# ReflowController.net
KiCad netlist of a schematic drawn in EAGLE
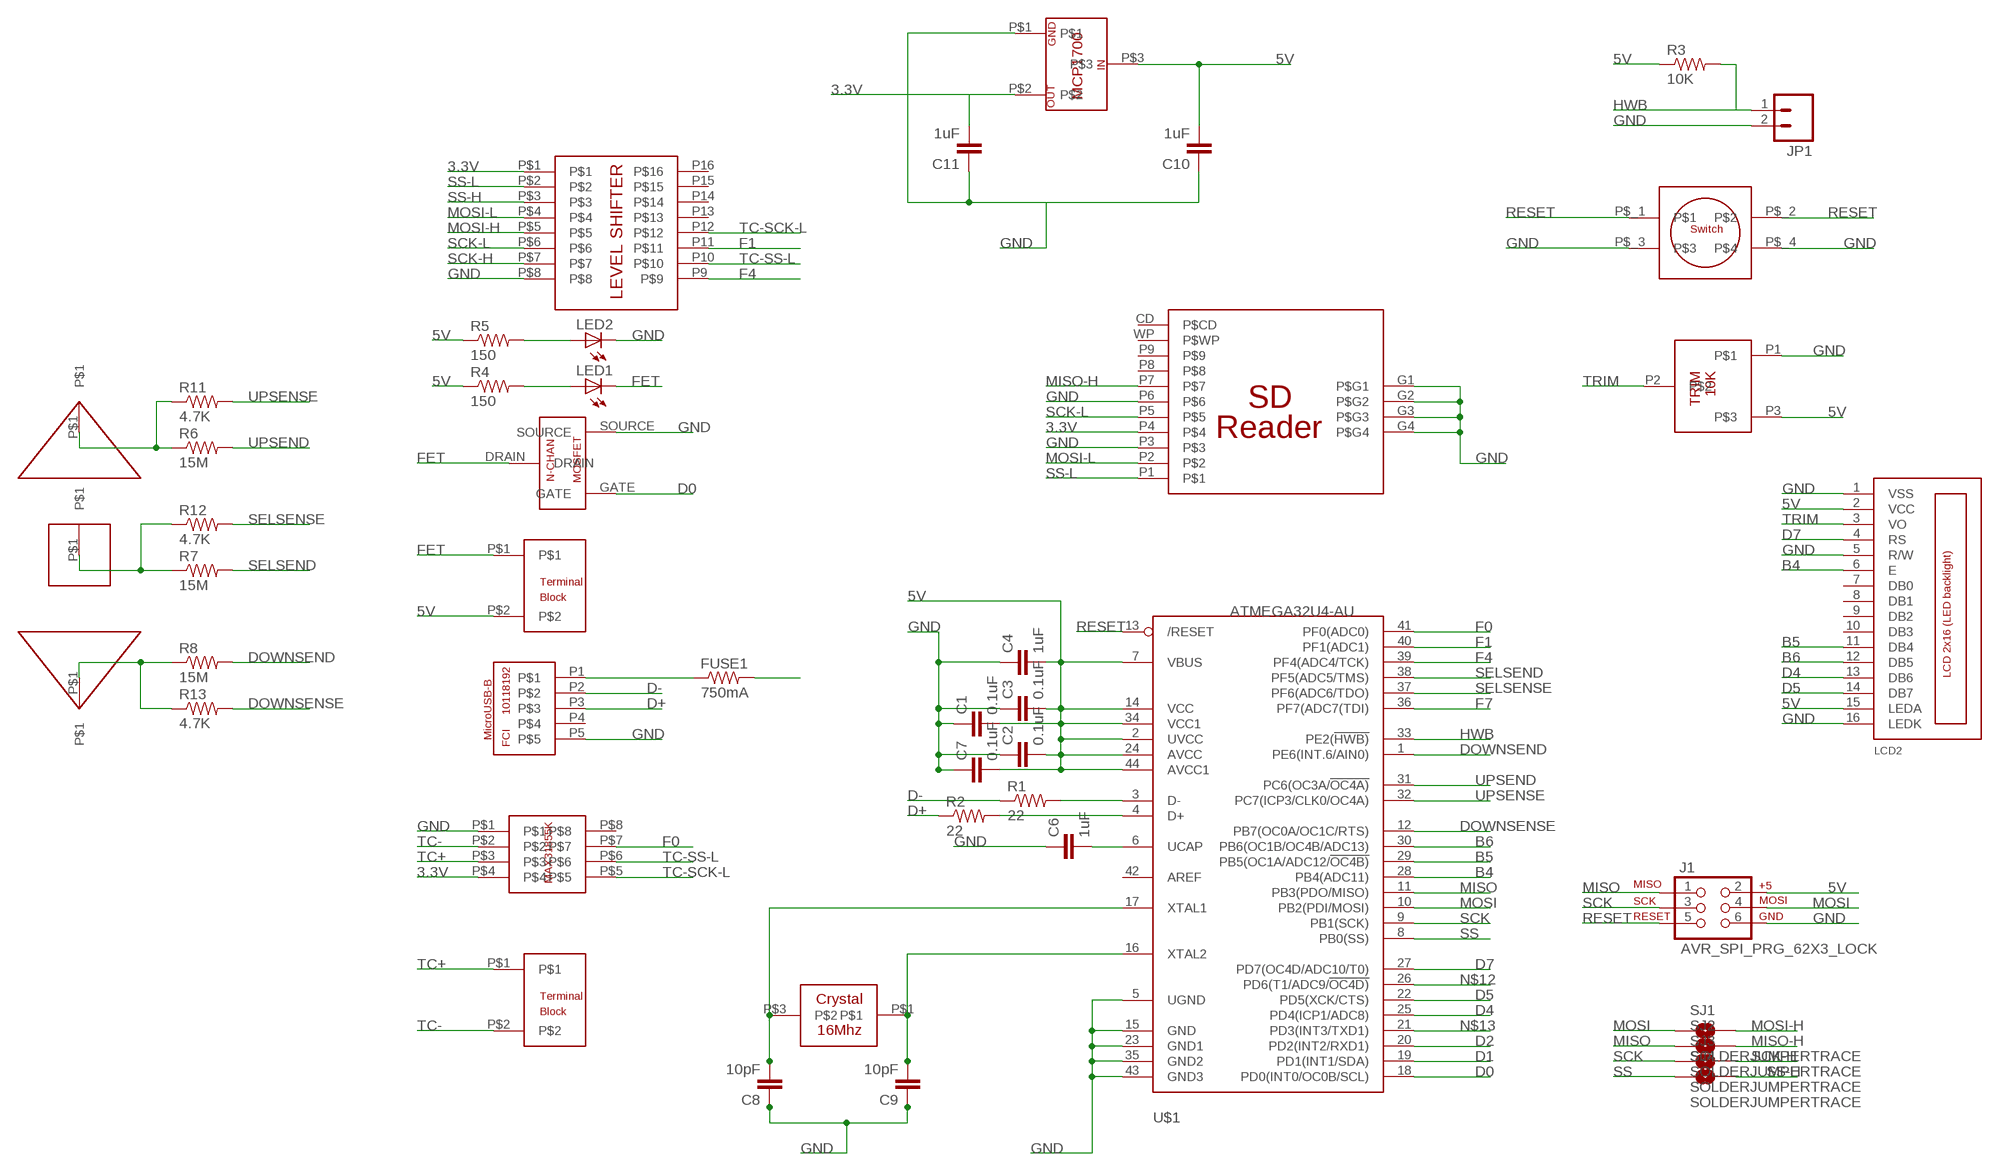
[diagram p0: schematic, sheet 1]

(export (version "E")
  (design (tool "Eeschema 10.0.6"))
  (components
    (comp (ref "C1")
      (value "0.1uF")
      (footprint "eagle-import:0603-CAP")
      (libsource (lib "eagle-import") (part "CAP0603-CAP"))
    )
    (comp (ref "C2")
      (value "0.1uF")
      (footprint "eagle-import:0603-CAP")
      (libsource (lib "eagle-import") (part "CAP0603-CAP"))
    )
    (comp (ref "C3")
      (value "0.1uF")
      (footprint "eagle-import:0603-CAP")
      (libsource (lib "eagle-import") (part "CAP0603-CAP"))
    )
    (comp (ref "C4")
      (value "1uF")
      (footprint "eagle-import:0603-CAP")
      (libsource (lib "eagle-import") (part "CAP0603-CAP"))
    )
    (comp (ref "C6")
      (value "1uF")
      (footprint "eagle-import:0603-CAP")
      (libsource (lib "eagle-import") (part "CAP0603-CAP"))
    )
    (comp (ref "C7")
      (value "0.1uF")
      (footprint "eagle-import:0603-CAP")
      (libsource (lib "eagle-import") (part "CAP0603-CAP"))
    )
    (comp (ref "C8")
      (value "10pF")
      (footprint "eagle-import:0603-CAP")
      (libsource (lib "eagle-import") (part "CAP0603-CAP"))
    )
    (comp (ref "C9")
      (value "10pF")
      (footprint "eagle-import:0603-CAP")
      (libsource (lib "eagle-import") (part "CAP0603-CAP"))
    )
    (comp (ref "C10")
      (value "1uF")
      (footprint "eagle-import:0603-CAP")
      (libsource (lib "eagle-import") (part "CAP0603-CAP"))
    )
    (comp (ref "C11")
      (value "1uF")
      (footprint "eagle-import:0603-CAP")
      (libsource (lib "eagle-import") (part "CAP0603-CAP"))
    )
    (comp (ref "FUSE1")
      (value "750mA")
      (footprint "eagle-import:0603-RES")
      (libsource (lib "eagle-import") (part "RESISTOR0603-RES"))
    )
    (comp (ref "J1")
      (value "AVR_SPI_PRG_62X3_LOCK")
      (footprint "eagle-import:2X3_LOCK")
      (libsource (lib "eagle-import") (part "AVR_SPI_PRG_62X3_LOCK"))
    )
    (comp (ref "JP1")
      (value "M02PTH")
      (footprint "eagle-import:1X02")
      (libsource (lib "eagle-import") (part "M02PTH"))
    )
    (comp (ref "LCD2")
      (value "LCD_2X16_SIL")
      (footprint "eagle-import:HY-1602F")
      (libsource (lib "eagle-import") (part "LCD_2X16_SIL"))
    )
    (comp (ref "LED1")
      (value "LED0603")
      (footprint "eagle-import:LED-0603")
      (libsource (lib "eagle-import") (part "LED0603"))
    )
    (comp (ref "LED2")
      (value "LED0603")
      (footprint "eagle-import:LED-0603")
      (libsource (lib "eagle-import") (part "LED0603"))
    )
    (comp (ref "R1")
      (value "22")
      (footprint "eagle-import:0603-RES")
      (libsource (lib "eagle-import") (part "RESISTOR0603-RES"))
    )
    (comp (ref "R2")
      (value "22")
      (footprint "eagle-import:0603-RES")
      (libsource (lib "eagle-import") (part "RESISTOR0603-RES"))
    )
    (comp (ref "R3")
      (value "10K")
      (footprint "eagle-import:0603-RES")
      (libsource (lib "eagle-import") (part "RESISTOR0603-RES"))
    )
    (comp (ref "R4")
      (value "150")
      (footprint "eagle-import:0603-RES")
      (libsource (lib "eagle-import") (part "RESISTOR0603-RES"))
    )
    (comp (ref "R5")
      (value "150")
      (footprint "eagle-import:0603-RES")
      (libsource (lib "eagle-import") (part "RESISTOR0603-RES"))
    )
    (comp (ref "R6")
      (value "15M")
      (footprint "eagle-import:0603-RES")
      (libsource (lib "eagle-import") (part "RESISTOR0603-RES"))
    )
    (comp (ref "R7")
      (value "15M")
      (footprint "eagle-import:0603-RES")
      (libsource (lib "eagle-import") (part "RESISTOR0603-RES"))
    )
    (comp (ref "R8")
      (value "15M")
      (footprint "eagle-import:0603-RES")
      (libsource (lib "eagle-import") (part "RESISTOR0603-RES"))
    )
    (comp (ref "R11")
      (value "4.7K")
      (footprint "eagle-import:0603-RES")
      (libsource (lib "eagle-import") (part "RESISTOR0603-RES"))
    )
    (comp (ref "R12")
      (value "4.7K")
      (footprint "eagle-import:0603-RES")
      (libsource (lib "eagle-import") (part "RESISTOR0603-RES"))
    )
    (comp (ref "R13")
      (value "4.7K")
      (footprint "eagle-import:0603-RES")
      (libsource (lib "eagle-import") (part "RESISTOR0603-RES"))
    )
    (comp (ref "SJ1")
      (value "SOLDERJUMPERTRACE")
      (footprint "eagle-import:SJ_2S-TRACE")
      (libsource (lib "eagle-import") (part "SOLDERJUMPERTRACE"))
    )
    (comp (ref "SJ2")
      (value "SOLDERJUMPERTRACE")
      (footprint "eagle-import:SJ_2S-TRACE")
      (libsource (lib "eagle-import") (part "SOLDERJUMPERTRACE"))
    )
    (comp (ref "SJ3")
      (value "SOLDERJUMPERTRACE")
      (footprint "eagle-import:SJ_2S-TRACE")
      (libsource (lib "eagle-import") (part "SOLDERJUMPERTRACE"))
    )
    (comp (ref "SJ4")
      (value "SOLDERJUMPERTRACE")
      (footprint "eagle-import:SJ_2S-TRACE")
      (libsource (lib "eagle-import") (part "SOLDERJUMPERTRACE"))
    )
    (comp (ref "U$1")
      (value "ATMEGA32U4-AU")
      (footprint "eagle-import:TQFP44")
      (libsource (lib "eagle-import") (part "ATMEGA32U4-AU"))
    )
    (comp (ref "U$2")
      (value "16MHZ-CRYSTAL_NX3225GA-16.000M-STD-CRG-1")
      (footprint "eagle-import:16MHZ-CRYSTAL_NX3225GA-16.000M-STD-CRG-1")
      (libsource (lib "eagle-import") (part "16MHZ-CRYSTAL_NX3225GA-16.000M-STD-CRG-1"))
    )
    (comp (ref "U$3")
      (value "USB-B_10118192-0001LF")
      (footprint "eagle-import:USB-B_10118192-0001LF")
      (libsource (lib "eagle-import") (part "USB-B_10118192-0001LF"))
    )
    (comp (ref "U$4")
      (value "SDREADER_2041021-4")
      (footprint "eagle-import:SDREADER_2041021-4")
      (libsource (lib "eagle-import") (part "SDREADER_2041021-4"))
    )
    (comp (ref "U$5")
      (value "2POS_TERM_ED2748-ND")
      (footprint "eagle-import:2POS_TERM_ED2748-ND")
      (libsource (lib "eagle-import") (part "2POS_TERM_ED2748-ND"))
    )
    (comp (ref "U$6")
      (value "N-MOSFET630_DMG1012T-7DICT-ND")
      (footprint "eagle-import:N-MOSFET630_DMG1012T-7DICT-ND")
      (libsource (lib "eagle-import") (part "N-MOSFET630_DMG1012T-7DICT-ND"))
    )
    (comp (ref "U$7")
      (value "2POS_TERM_ED2748-ND")
      (footprint "eagle-import:2POS_TERM_ED2748-ND")
      (libsource (lib "eagle-import") (part "2POS_TERM_ED2748-ND"))
    )
    (comp (ref "U$8")
      (value "NXP_LVL_SHIFT_74HC4050D,653")
      (footprint "eagle-import:NXP_LVL_SHIFT_74HC4050D,653")
      (libsource (lib "eagle-import") (part "NXP_LVL_SHIFT_74HC4050D,653"))
    )
    (comp (ref "U$9")
      (value "MAX_TC_MAX31855KASA+")
      (footprint "eagle-import:MAX_TC_MAX31855KASA+")
      (libsource (lib "eagle-import") (part "MAX_TC_MAX31855KASA+"))
    )
    (comp (ref "U$10")
      (value "10K_TRIM_3362F-1-103LF")
      (footprint "eagle-import:10K_TRIM_3362F-1-103LF")
      (libsource (lib "eagle-import") (part "10K_TRIM_3362F-1-103LF"))
    )
    (comp (ref "U$11")
      (value "MCP1700__LDO")
      (footprint "eagle-import:MCP1700__LDO")
      (libsource (lib "eagle-import") (part "MCP1700__LDO"))
    )
    (comp (ref "U$12")
      (value "MOM-SWITCH-EG4620CT-ND")
      (footprint "eagle-import:MOM-SWITCH-EG4620CT-ND")
      (libsource (lib "eagle-import") (part "MOM-SWITCH-EG4620CT-ND"))
    )
    (comp (ref "U$13")
      (value "CAPTOUCH_ARROW")
      (footprint "eagle-import:CAPTOUCH_ARROW")
      (libsource (lib "eagle-import") (part "CAPTOUCH_ARROW"))
    )
    (comp (ref "U$14")
      (value "CAPTOUCH_ARROW")
      (footprint "eagle-import:CAPTOUCH_ARROW")
      (libsource (lib "eagle-import") (part "CAPTOUCH_ARROW"))
    )
    (comp (ref "U$15")
      (value "CAPTOUCH_SQUARE")
      (footprint "eagle-import:CAPTOUCH_SQUARE")
      (libsource (lib "eagle-import") (part "CAPTOUCH_SQUARE"))
    )
  )
  (nets
    (net (code "1") (name "/3.3V") (class "Default")
      (node (ref "C11") (pin "2") (pinfunction "2_2") (pintype "passive"))
      (node (ref "U$11") (pin "P$2") (pinfunction "P$2_P$2") (pintype "bidirectional"))
      (node (ref "U$4") (pin "P4") (pinfunction "P$4_P4") (pintype "bidirectional"))
      (node (ref "U$8") (pin "P$1") (pinfunction "P$1_P$1") (pintype "bidirectional"))
      (node (ref "U$9") (pin "P$4") (pinfunction "P$4_P$4") (pintype "bidirectional"))
    )
    (net (code "2") (name "/5V") (class "Default")
      (node (ref "C1") (pin "2") (pinfunction "2_2") (pintype "passive"))
      (node (ref "C10") (pin "2") (pinfunction "2_2") (pintype "passive"))
      (node (ref "C2") (pin "2") (pinfunction "2_2") (pintype "passive"))
      (node (ref "C3") (pin "2") (pinfunction "2_2") (pintype "passive"))
      (node (ref "C4") (pin "2") (pinfunction "2_2") (pintype "passive"))
      (node (ref "C7") (pin "2") (pinfunction "2_2") (pintype "passive"))
      (node (ref "FUSE1") (pin "2") (pinfunction "2_2") (pintype "passive"))
      (node (ref "J1") (pin "2") (pinfunction "2_2") (pintype "passive"))
      (node (ref "LCD2") (pin "15") (pinfunction "LEDA_15") (pintype "passive"))
      (node (ref "LCD2") (pin "2") (pinfunction "VCC_2") (pintype "power_in"))
      (node (ref "R3") (pin "1") (pinfunction "1_1") (pintype "passive"))
      (node (ref "R4") (pin "1") (pinfunction "1_1") (pintype "passive"))
      (node (ref "R5") (pin "1") (pinfunction "1_1") (pintype "passive"))
      (node (ref "U$1") (pin "14") (pinfunction "VCC_14") (pintype "bidirectional"))
      (node (ref "U$1") (pin "2") (pinfunction "UVCC_2") (pintype "bidirectional"))
      (node (ref "U$1") (pin "24") (pinfunction "AVCC_24") (pintype "bidirectional"))
      (node (ref "U$1") (pin "34") (pinfunction "VCC1_34") (pintype "bidirectional"))
      (node (ref "U$1") (pin "44") (pinfunction "AVCC1_44") (pintype "bidirectional"))
      (node (ref "U$1") (pin "7") (pinfunction "VBUS_7") (pintype "bidirectional"))
      (node (ref "U$10") (pin "P3") (pinfunction "P$3_P3") (pintype "bidirectional"))
      (node (ref "U$11") (pin "P$3") (pinfunction "P$3_P$3") (pintype "bidirectional"))
      (node (ref "U$5") (pin "P$2") (pinfunction "P$2_P$2") (pintype "bidirectional"))
    )
    (net (code "3") (name "/B4") (class "Default")
      (node (ref "LCD2") (pin "6") (pinfunction "E_6") (pintype "input"))
      (node (ref "U$1") (pin "28") (pinfunction "PB4(ADC11)_28") (pintype "bidirectional"))
    )
    (net (code "4") (name "/B5") (class "Default")
      (node (ref "LCD2") (pin "11") (pinfunction "DB4_11") (pintype "bidirectional"))
      (node (ref "U$1") (pin "29") (pinfunction "PB5(OC1A/ADC12/~{OC4B})_29") (pintype "bidirectional"))
    )
    (net (code "5") (name "/B6") (class "Default")
      (node (ref "LCD2") (pin "12") (pinfunction "DB5_12") (pintype "bidirectional"))
      (node (ref "U$1") (pin "30") (pinfunction "PB6(OC1B/OC4B/ADC13)_30") (pintype "bidirectional"))
    )
    (net (code "6") (name "/D+") (class "Default")
      (node (ref "R2") (pin "1") (pinfunction "1_1") (pintype "passive"))
      (node (ref "U$3") (pin "P3") (pinfunction "P$3_P3") (pintype "bidirectional"))
    )
    (net (code "7") (name "/D-") (class "Default")
      (node (ref "R1") (pin "1") (pinfunction "1_1") (pintype "passive"))
      (node (ref "U$3") (pin "P2") (pinfunction "P$2_P2") (pintype "bidirectional"))
    )
    (net (code "8") (name "/D0") (class "Default")
      (node (ref "U$1") (pin "18") (pinfunction "PD0(INT0/OC0B/SCL)_18") (pintype "bidirectional"))
      (node (ref "U$6") (pin "GATE") (pinfunction "GATE_GATE") (pintype "bidirectional"))
    )
    (net (code "9") (name "/D1") (class "Default")
      (node (ref "U$1") (pin "19") (pinfunction "PD1(INT1/SDA)_19") (pintype "bidirectional"))
    )
    (net (code "10") (name "/D2") (class "Default")
      (node (ref "U$1") (pin "20") (pinfunction "PD2(INT2/RXD1)_20") (pintype "bidirectional"))
    )
    (net (code "11") (name "/D4") (class "Default")
      (node (ref "LCD2") (pin "13") (pinfunction "DB6_13") (pintype "bidirectional"))
      (node (ref "U$1") (pin "25") (pinfunction "PD4(ICP1/ADC8)_25") (pintype "bidirectional"))
    )
    (net (code "12") (name "/D5") (class "Default")
      (node (ref "LCD2") (pin "14") (pinfunction "DB7_14") (pintype "bidirectional"))
      (node (ref "U$1") (pin "22") (pinfunction "PD5(XCK/CTS)_22") (pintype "bidirectional"))
    )
    (net (code "13") (name "/D7") (class "Default")
      (node (ref "LCD2") (pin "4") (pinfunction "RS_4") (pintype "input"))
      (node (ref "U$1") (pin "27") (pinfunction "PD7(OC4D/ADC10/T0)_27") (pintype "bidirectional"))
    )
    (net (code "14") (name "/DOWNSEND") (class "Default")
      (node (ref "R8") (pin "2") (pinfunction "2_2") (pintype "passive"))
      (node (ref "U$1") (pin "1") (pinfunction "PE6(INT.6/AIN0)_1") (pintype "bidirectional"))
    )
    (net (code "15") (name "/DOWNSENSE") (class "Default")
      (node (ref "R13") (pin "2") (pinfunction "2_2") (pintype "passive"))
      (node (ref "U$1") (pin "12") (pinfunction "PB7(OC0A/OC1C/RTS)_12") (pintype "bidirectional"))
    )
    (net (code "16") (name "/F0") (class "Default")
      (node (ref "U$1") (pin "41") (pinfunction "PF0(ADC0)_41") (pintype "bidirectional"))
      (node (ref "U$9") (pin "P$7") (pinfunction "P$7_P$7") (pintype "bidirectional"))
    )
    (net (code "17") (name "/F1") (class "Default")
      (node (ref "U$1") (pin "40") (pinfunction "PF1(ADC1)_40") (pintype "bidirectional"))
      (node (ref "U$8") (pin "P11") (pinfunction "P$11_P11") (pintype "bidirectional"))
    )
    (net (code "18") (name "/F4") (class "Default")
      (node (ref "U$1") (pin "39") (pinfunction "PF4(ADC4/TCK)_39") (pintype "bidirectional"))
      (node (ref "U$8") (pin "P9") (pinfunction "P$9_P9") (pintype "bidirectional"))
    )
    (net (code "19") (name "/F7") (class "Default")
      (node (ref "U$1") (pin "36") (pinfunction "PF7(ADC7(TDI)_36") (pintype "bidirectional"))
    )
    (net (code "20") (name "/FET") (class "Default")
      (node (ref "LED1") (pin "C") (pinfunction "C_C") (pintype "passive"))
      (node (ref "U$5") (pin "P$1") (pinfunction "P$1_P$1") (pintype "bidirectional"))
      (node (ref "U$6") (pin "DRAIN") (pinfunction "DRAIN_DRAIN") (pintype "bidirectional"))
    )
    (net (code "21") (name "/GND") (class "Default")
      (node (ref "C1") (pin "1") (pinfunction "1_1") (pintype "passive"))
      (node (ref "C10") (pin "1") (pinfunction "1_1") (pintype "passive"))
      (node (ref "C11") (pin "1") (pinfunction "1_1") (pintype "passive"))
      (node (ref "C2") (pin "1") (pinfunction "1_1") (pintype "passive"))
      (node (ref "C3") (pin "1") (pinfunction "1_1") (pintype "passive"))
      (node (ref "C4") (pin "1") (pinfunction "1_1") (pintype "passive"))
      (node (ref "C6") (pin "1") (pinfunction "1_1") (pintype "passive"))
      (node (ref "C7") (pin "1") (pinfunction "1_1") (pintype "passive"))
      (node (ref "C8") (pin "1") (pinfunction "1_1") (pintype "passive"))
      (node (ref "C9") (pin "1") (pinfunction "1_1") (pintype "passive"))
      (node (ref "J1") (pin "6") (pinfunction "6_6") (pintype "passive"))
      (node (ref "JP1") (pin "2") (pinfunction "2_2") (pintype "passive"))
      (node (ref "LCD2") (pin "1") (pinfunction "VSS_1") (pintype "power_in"))
      (node (ref "LCD2") (pin "16") (pinfunction "LEDK_16") (pintype "passive"))
      (node (ref "LCD2") (pin "5") (pinfunction "R/W_5") (pintype "input"))
      (node (ref "LED2") (pin "C") (pinfunction "C_C") (pintype "passive"))
      (node (ref "U$1") (pin "15") (pinfunction "GND_15") (pintype "bidirectional"))
      (node (ref "U$1") (pin "23") (pinfunction "GND1_23") (pintype "bidirectional"))
      (node (ref "U$1") (pin "35") (pinfunction "GND2_35") (pintype "bidirectional"))
      (node (ref "U$1") (pin "43") (pinfunction "GND3_43") (pintype "bidirectional"))
      (node (ref "U$1") (pin "5") (pinfunction "UGND_5") (pintype "bidirectional"))
      (node (ref "U$10") (pin "P1") (pinfunction "P$1_P1") (pintype "bidirectional"))
      (node (ref "U$11") (pin "P$1") (pinfunction "P$1_P$1") (pintype "bidirectional"))
      (node (ref "U$12") (pin "P$_3") (pinfunction "P$3_P$_3") (pintype "bidirectional"))
      (node (ref "U$12") (pin "P$_4") (pinfunction "P$4_P$_4") (pintype "bidirectional"))
      (node (ref "U$3") (pin "P5") (pinfunction "P$5_P5") (pintype "bidirectional"))
      (node (ref "U$4") (pin "G1") (pinfunction "P$G1_G1") (pintype "bidirectional"))
      (node (ref "U$4") (pin "G2") (pinfunction "P$G2_G2") (pintype "bidirectional"))
      (node (ref "U$4") (pin "G3") (pinfunction "P$G3_G3") (pintype "bidirectional"))
      (node (ref "U$4") (pin "G4") (pinfunction "P$G4_G4") (pintype "bidirectional"))
      (node (ref "U$4") (pin "P3") (pinfunction "P$3_P3") (pintype "bidirectional"))
      (node (ref "U$4") (pin "P6") (pinfunction "P$6_P6") (pintype "bidirectional"))
      (node (ref "U$6") (pin "SOURCE") (pinfunction "SOURCE_SOURCE") (pintype "bidirectional"))
      (node (ref "U$8") (pin "P$8") (pinfunction "P$8_P$8") (pintype "bidirectional"))
      (node (ref "U$9") (pin "P$1") (pinfunction "P$1_P$1") (pintype "bidirectional"))
    )
    (net (code "22") (name "/HWB") (class "Default")
      (node (ref "JP1") (pin "1") (pinfunction "1_1") (pintype "passive"))
      (node (ref "R3") (pin "2") (pinfunction "2_2") (pintype "passive"))
      (node (ref "U$1") (pin "33") (pinfunction "PE2(~{HWB})_33") (pintype "bidirectional"))
    )
    (net (code "23") (name "/MISO") (class "Default")
      (node (ref "J1") (pin "1") (pinfunction "1_1") (pintype "passive"))
      (node (ref "SJ2") (pin "1") (pinfunction "1_1") (pintype "passive"))
      (node (ref "U$1") (pin "11") (pinfunction "PB3(PDO/MISO)_11") (pintype "bidirectional"))
    )
    (net (code "24") (name "/MISO-H") (class "Default")
      (node (ref "SJ2") (pin "2") (pinfunction "2_2") (pintype "passive"))
      (node (ref "U$4") (pin "P7") (pinfunction "P$7_P7") (pintype "bidirectional"))
    )
    (net (code "25") (name "/MOSI") (class "Default")
      (node (ref "J1") (pin "4") (pinfunction "4_4") (pintype "passive"))
      (node (ref "SJ1") (pin "1") (pinfunction "1_1") (pintype "passive"))
      (node (ref "U$1") (pin "10") (pinfunction "PB2(PDI/MOSI)_10") (pintype "bidirectional"))
    )
    (net (code "26") (name "/MOSI-H") (class "Default")
      (node (ref "SJ1") (pin "2") (pinfunction "2_2") (pintype "passive"))
      (node (ref "U$8") (pin "P$5") (pinfunction "P$5_P$5") (pintype "bidirectional"))
    )
    (net (code "27") (name "/MOSI-L") (class "Default")
      (node (ref "U$4") (pin "P2") (pinfunction "P$2_P2") (pintype "bidirectional"))
      (node (ref "U$8") (pin "P$4") (pinfunction "P$4_P$4") (pintype "bidirectional"))
    )
    (net (code "28") (name "/N$12") (class "Default")
      (node (ref "U$1") (pin "26") (pinfunction "PD6(T1/ADC9/~{OC4D})_26") (pintype "bidirectional"))
    )
    (net (code "29") (name "/N$13") (class "Default")
      (node (ref "U$1") (pin "21") (pinfunction "PD3(INT3/TXD1)_21") (pintype "bidirectional"))
    )
    (net (code "30") (name "/RESET") (class "Default")
      (node (ref "J1") (pin "5") (pinfunction "5_5") (pintype "passive"))
      (node (ref "U$1") (pin "13") (pinfunction "/RESET_13") (pintype "bidirectional"))
      (node (ref "U$12") (pin "P$_1") (pinfunction "P$1_P$_1") (pintype "bidirectional"))
      (node (ref "U$12") (pin "P$_2") (pinfunction "P$2_P$_2") (pintype "bidirectional"))
    )
    (net (code "31") (name "/SCK") (class "Default")
      (node (ref "J1") (pin "3") (pinfunction "3_3") (pintype "passive"))
      (node (ref "SJ3") (pin "1") (pinfunction "1_1") (pintype "passive"))
      (node (ref "U$1") (pin "9") (pinfunction "PB1(SCK)_9") (pintype "bidirectional"))
    )
    (net (code "32") (name "/SCK-H") (class "Default")
      (node (ref "SJ3") (pin "2") (pinfunction "2_2") (pintype "passive"))
      (node (ref "U$8") (pin "P$7") (pinfunction "P$7_P$7") (pintype "bidirectional"))
    )
    (net (code "33") (name "/SCK-L") (class "Default")
      (node (ref "U$4") (pin "P5") (pinfunction "P$5_P5") (pintype "bidirectional"))
      (node (ref "U$8") (pin "P$6") (pinfunction "P$6_P$6") (pintype "bidirectional"))
    )
    (net (code "34") (name "/SELSEND") (class "Default")
      (node (ref "R7") (pin "2") (pinfunction "2_2") (pintype "passive"))
      (node (ref "U$1") (pin "38") (pinfunction "PF5(ADC5/TMS)_38") (pintype "bidirectional"))
    )
    (net (code "35") (name "/SELSENSE") (class "Default")
      (node (ref "R12") (pin "2") (pinfunction "2_2") (pintype "passive"))
      (node (ref "U$1") (pin "37") (pinfunction "PF6(ADC6/TDO)_37") (pintype "bidirectional"))
    )
    (net (code "36") (name "/SS") (class "Default")
      (node (ref "SJ4") (pin "1") (pinfunction "1_1") (pintype "passive"))
      (node (ref "U$1") (pin "8") (pinfunction "PB0(SS)_8") (pintype "bidirectional"))
    )
    (net (code "37") (name "/SS-H") (class "Default")
      (node (ref "SJ4") (pin "2") (pinfunction "2_2") (pintype "passive"))
      (node (ref "U$8") (pin "P$3") (pinfunction "P$3_P$3") (pintype "bidirectional"))
    )
    (net (code "38") (name "/SS-L") (class "Default")
      (node (ref "U$4") (pin "P1") (pinfunction "P$1_P1") (pintype "bidirectional"))
      (node (ref "U$8") (pin "P$2") (pinfunction "P$2_P$2") (pintype "bidirectional"))
    )
    (net (code "39") (name "/TC+") (class "Default")
      (node (ref "U$7") (pin "P$1") (pinfunction "P$1_P$1") (pintype "bidirectional"))
      (node (ref "U$9") (pin "P$3") (pinfunction "P$3_P$3") (pintype "bidirectional"))
    )
    (net (code "40") (name "/TC-") (class "Default")
      (node (ref "U$7") (pin "P$2") (pinfunction "P$2_P$2") (pintype "bidirectional"))
      (node (ref "U$9") (pin "P$2") (pinfunction "P$2_P$2") (pintype "bidirectional"))
    )
    (net (code "41") (name "/TC-SCK-L") (class "Default")
      (node (ref "U$8") (pin "P12") (pinfunction "P$12_P12") (pintype "bidirectional"))
      (node (ref "U$9") (pin "P$5") (pinfunction "P$5_P$5") (pintype "bidirectional"))
    )
    (net (code "42") (name "/TC-SS-L") (class "Default")
      (node (ref "U$8") (pin "P10") (pinfunction "P$10_P10") (pintype "bidirectional"))
      (node (ref "U$9") (pin "P$6") (pinfunction "P$6_P$6") (pintype "bidirectional"))
    )
    (net (code "43") (name "/TRIM") (class "Default")
      (node (ref "LCD2") (pin "3") (pinfunction "VO_3") (pintype "input"))
      (node (ref "U$10") (pin "P2") (pinfunction "P$2_P2") (pintype "bidirectional"))
    )
    (net (code "44") (name "/UPSEND") (class "Default")
      (node (ref "R6") (pin "2") (pinfunction "2_2") (pintype "passive"))
      (node (ref "U$1") (pin "31") (pinfunction "PC6(OC3A/~{OC4A})_31") (pintype "bidirectional"))
    )
    (net (code "45") (name "/UPSENSE") (class "Default")
      (node (ref "R11") (pin "2") (pinfunction "2_2") (pintype "passive"))
      (node (ref "U$1") (pin "32") (pinfunction "PC7(ICP3/CLK0/OC4A)_32") (pintype "bidirectional"))
    )
    (net (code "46") (name "Net-(LED1-PadA)") (class "Default")
      (node (ref "LED1") (pin "A") (pinfunction "A_A") (pintype "passive"))
      (node (ref "R4") (pin "2") (pinfunction "2_2") (pintype "passive"))
    )
    (net (code "47") (name "Net-(LED2-PadA)") (class "Default")
      (node (ref "LED2") (pin "A") (pinfunction "A_A") (pintype "passive"))
      (node (ref "R5") (pin "2") (pinfunction "2_2") (pintype "passive"))
    )
    (net (code "48") (name "Net-(R11-Pad1)") (class "Default")
      (node (ref "R11") (pin "1") (pinfunction "1_1") (pintype "passive"))
      (node (ref "R6") (pin "1") (pinfunction "1_1") (pintype "passive"))
      (node (ref "U$13") (pin "P$1") (pinfunction "P$1_P$1") (pintype "bidirectional"))
    )
    (net (code "49") (name "Net-(R12-Pad1)") (class "Default")
      (node (ref "R12") (pin "1") (pinfunction "1_1") (pintype "passive"))
      (node (ref "R7") (pin "1") (pinfunction "1_1") (pintype "passive"))
      (node (ref "U$15") (pin "P$1") (pinfunction "P$1_P$1") (pintype "bidirectional"))
    )
    (net (code "50") (name "Net-(R13-Pad1)") (class "Default")
      (node (ref "R13") (pin "1") (pinfunction "1_1") (pintype "passive"))
      (node (ref "R8") (pin "1") (pinfunction "1_1") (pintype "passive"))
      (node (ref "U$14") (pin "P$1") (pinfunction "P$1_P$1") (pintype "bidirectional"))
    )
    (net (code "51") (name "Net-(U$1-D+)") (class "Default")
      (node (ref "R2") (pin "2") (pinfunction "2_2") (pintype "passive"))
      (node (ref "U$1") (pin "4") (pinfunction "D+_4") (pintype "bidirectional"))
    )
    (net (code "52") (name "Net-(U$1-D-)") (class "Default")
      (node (ref "R1") (pin "2") (pinfunction "2_2") (pintype "passive"))
      (node (ref "U$1") (pin "3") (pinfunction "D-_3") (pintype "bidirectional"))
    )
    (net (code "53") (name "Net-(U$1-UCAP)") (class "Default")
      (node (ref "C6") (pin "2") (pinfunction "2_2") (pintype "passive"))
      (node (ref "U$1") (pin "6") (pinfunction "UCAP_6") (pintype "bidirectional"))
    )
    (net (code "54") (name "Net-(U$1-XTAL1)") (class "Default")
      (node (ref "C8") (pin "2") (pinfunction "2_2") (pintype "passive"))
      (node (ref "U$1") (pin "17") (pinfunction "XTAL1_17") (pintype "bidirectional"))
      (node (ref "U$2") (pin "P$3") (pinfunction "P$2_P$3") (pintype "bidirectional"))
    )
    (net (code "55") (name "Net-(U$1-XTAL2)") (class "Default")
      (node (ref "C9") (pin "2") (pinfunction "2_2") (pintype "passive"))
      (node (ref "U$1") (pin "16") (pinfunction "XTAL2_16") (pintype "bidirectional"))
      (node (ref "U$2") (pin "P$1") (pinfunction "P$1_P$1") (pintype "bidirectional"))
    )
    (net (code "56") (name "Net-(U$3-P$1)") (class "Default")
      (node (ref "FUSE1") (pin "1") (pinfunction "1_1") (pintype "passive"))
      (node (ref "U$3") (pin "P1") (pinfunction "P$1_P1") (pintype "bidirectional"))
    )
    (net (code "57") (name "unconnected-(LCD2-DB0-Pad7)") (class "Default")
      (node (ref "LCD2") (pin "7") (pinfunction "DB0_7") (pintype "bidirectional"))
    )
    (net (code "58") (name "unconnected-(LCD2-DB1-Pad8)") (class "Default")
      (node (ref "LCD2") (pin "8") (pinfunction "DB1_8") (pintype "bidirectional"))
    )
    (net (code "59") (name "unconnected-(LCD2-DB2-Pad9)") (class "Default")
      (node (ref "LCD2") (pin "9") (pinfunction "DB2_9") (pintype "bidirectional"))
    )
    (net (code "60") (name "unconnected-(LCD2-DB3-Pad10)") (class "Default")
      (node (ref "LCD2") (pin "10") (pinfunction "DB3_10") (pintype "bidirectional"))
    )
    (net (code "61") (name "unconnected-(U$1-AREF-Pad42)") (class "Default")
      (node (ref "U$1") (pin "42") (pinfunction "AREF_42") (pintype "bidirectional"))
    )
    (net (code "62") (name "unconnected-(U$3-P$4-PadP4)") (class "Default")
      (node (ref "U$3") (pin "P4") (pinfunction "P$4_P4") (pintype "bidirectional"))
    )
    (net (code "63") (name "unconnected-(U$4-P$8-PadP8)") (class "Default")
      (node (ref "U$4") (pin "P8") (pinfunction "P$8_P8") (pintype "bidirectional"))
    )
    (net (code "64") (name "unconnected-(U$4-P$9-PadP9)") (class "Default")
      (node (ref "U$4") (pin "P9") (pinfunction "P$9_P9") (pintype "bidirectional"))
    )
    (net (code "65") (name "unconnected-(U$4-P$CD-PadCD)") (class "Default")
      (node (ref "U$4") (pin "CD") (pinfunction "P$CD_CD") (pintype "bidirectional"))
    )
    (net (code "66") (name "unconnected-(U$4-P$WP-PadWP)") (class "Default")
      (node (ref "U$4") (pin "WP") (pinfunction "P$WP_WP") (pintype "bidirectional"))
    )
    (net (code "67") (name "unconnected-(U$8-P$13-PadP13)") (class "Default")
      (node (ref "U$8") (pin "P13") (pinfunction "P$13_P13") (pintype "bidirectional"))
    )
    (net (code "68") (name "unconnected-(U$8-P$14-PadP14)") (class "Default")
      (node (ref "U$8") (pin "P14") (pinfunction "P$14_P14") (pintype "bidirectional"))
    )
    (net (code "69") (name "unconnected-(U$8-P$15-PadP15)") (class "Default")
      (node (ref "U$8") (pin "P15") (pinfunction "P$15_P15") (pintype "bidirectional"))
    )
    (net (code "70") (name "unconnected-(U$8-P$16-PadP16)") (class "Default")
      (node (ref "U$8") (pin "P16") (pinfunction "P$16_P16") (pintype "bidirectional"))
    )
    (net (code "71") (name "unconnected-(U$9-PadP$8)") (class "Default")
      (node (ref "U$9") (pin "P$8") (pinfunction "P$8_P$8") (pintype "bidirectional"))
    )
  )
)
